# txrx_switch.net
KiCad netlist of a schematic drawn in Altium Designer
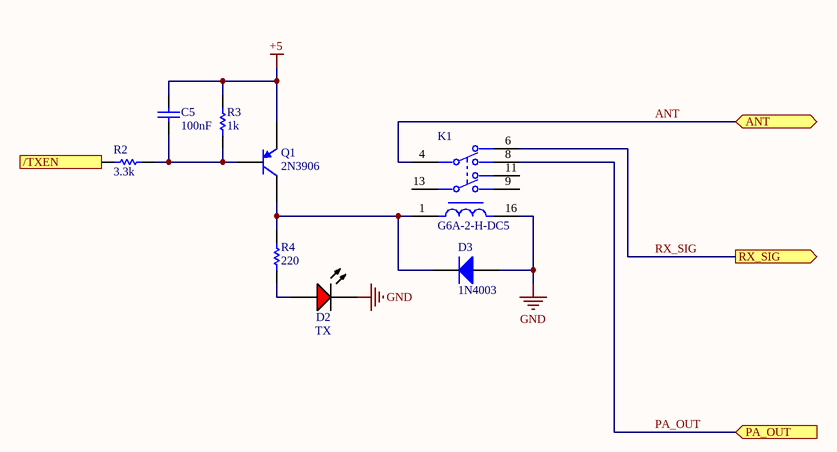
[diagram p0: txrx_switch.SchDoc]

(export (version "E")
  (design (tool "Eeschema 10.0.6"))
  (components
    (comp (ref "C5")
      (value "100nF")
      (footprint "RAD-0.1")
      (description "Capacitor")
      (fields (field (name "Comment") "Cap") (field (name "PUBLISHER") "Altium Limited"))
      (libsource (lib "Miscellaneous Devices") (part "Cap"))
    )
    (comp (ref "D2")
      (value "TX")
      (footprint "AVAG-HLMP-3301-2")
      (description "T-1 3/4 (5 mm) Diffused LED Lamp, 1.9 V, -40 to 100 degC, 2-Pin THD, RoHS, Bulk")
      (fields (field (name "MANUFACTURER") "Avago"))
      (libsource (lib "Altium Content Vault") (part "LED-RED-K1A2-2"))
    )
    (comp (ref "D3")
      (value "1N4003")
      (footprint "DIOD-DO-41-P-2_V")
      (description "1.0 A Rectifier, 15 pF, 200 V, -65 to 150 degC, 2-Pin DO-41 Plastic, RoHS, Tape and Reel")
      (fields (field (name "PARTNUMBER") "1N4003-T") (field (name "MANUFACTURER") "Diodes Inc"))
      (libsource (lib "Altium Content Vault") (part "DIOD-D-A1K2-2"))
    )
    (comp (ref "K1")
      (value "G6A-2-H-DC5")
      (footprint "FP-G6A-2-H-DC5-MFG")
      (description "RELAY GEN PURPOSE DPDT 2A 5VDC")
      (libsource (lib "Altium Content Vault") (part "26c8de10ccef747a418375544070044"))
    )
    (comp (ref "Q1")
      (value "2N3906")
      (footprint "TO-92A")
      (description "PNP General Purpose Amplifier")
      (fields (field (name "PUBLISHER") "Altium Limited"))
      (libsource (lib "Miscellaneous Devices") (part "2N3906"))
    )
    (comp (ref "R2")
      (value "3.3k")
      (footprint "AXIAL-0.4")
      (description "Resistor")
      (fields (field (name "Comment") "Res1") (field (name "PUBLISHER") "Altium Limited"))
      (libsource (lib "Miscellaneous Devices") (part "Res1"))
    )
    (comp (ref "R3")
      (value "1k")
      (footprint "AXIAL-0.4")
      (description "Resistor")
      (fields (field (name "Comment") "Res1") (field (name "PUBLISHER") "Altium Limited"))
      (libsource (lib "Miscellaneous Devices") (part "Res1"))
    )
    (comp (ref "R4")
      (value "220")
      (footprint "AXIAL-0.4")
      (description "Resistor")
      (fields (field (name "Comment") "Res1") (field (name "PUBLISHER") "Altium Limited"))
      (libsource (lib "Miscellaneous Devices") (part "Res1"))
    )
  )
  (nets
    (net (code "1") (name "+5") (class "Default")
      (node (ref "C5") (pin "1") (pinfunction "1_1") (pintype "passive"))
      (node (ref "Q1") (pin "1") (pinfunction "E_1") (pintype "passive"))
      (node (ref "R3") (pin "2") (pinfunction "2_2") (pintype "passive"))
    )
    (net (code "2") (name "/ANT") (class "Default")
      (node (ref "K1") (pin "4") (pinfunction "4_4") (pintype "passive"))
    )
    (net (code "3") (name "/PA_OUT") (class "Default")
      (node (ref "K1") (pin "8") (pinfunction "8_8") (pintype "passive"))
    )
    (net (code "4") (name "/RX_SIG") (class "Default")
      (node (ref "K1") (pin "6") (pinfunction "6_6") (pintype "passive"))
    )
    (net (code "5") (name "/{slash}TXEN") (class "Default")
      (node (ref "R2") (pin "1") (pinfunction "1_1") (pintype "passive"))
    )
    (net (code "6") (name "GND") (class "Default")
      (node (ref "D2") (pin "1") (pinfunction "K_1") (pintype "passive"))
      (node (ref "D3") (pin "1") (pinfunction "A_1") (pintype "passive"))
      (node (ref "K1") (pin "16") (pinfunction "16_16") (pintype "passive"))
    )
    (net (code "7") (name "Net-(D2-A)") (class "Default")
      (node (ref "D2") (pin "2") (pinfunction "A_2") (pintype "passive"))
      (node (ref "R4") (pin "1") (pinfunction "1_1") (pintype "passive"))
    )
    (net (code "8") (name "Net-(D3-K)") (class "Default")
      (node (ref "D3") (pin "2") (pinfunction "K_2") (pintype "passive"))
      (node (ref "K1") (pin "1") (pinfunction "1_1") (pintype "passive"))
      (node (ref "Q1") (pin "3") (pinfunction "C_3") (pintype "passive"))
      (node (ref "R4") (pin "2") (pinfunction "2_2") (pintype "passive"))
    )
    (net (code "9") (name "Net-(Q1-B)") (class "Default")
      (node (ref "C5") (pin "2") (pinfunction "2_2") (pintype "passive"))
      (node (ref "Q1") (pin "2") (pinfunction "B_2") (pintype "passive"))
      (node (ref "R2") (pin "2") (pinfunction "2_2") (pintype "passive"))
      (node (ref "R3") (pin "1") (pinfunction "1_1") (pintype "passive"))
    )
    (net (code "10") (name "unconnected-(K1-Pad9)") (class "Default")
      (node (ref "K1") (pin "9") (pinfunction "9_9") (pintype "passive"))
    )
    (net (code "11") (name "unconnected-(K1-Pad11)") (class "Default")
      (node (ref "K1") (pin "11") (pinfunction "11_11") (pintype "passive"))
    )
    (net (code "12") (name "unconnected-(K1-Pad13)") (class "Default")
      (node (ref "K1") (pin "13") (pinfunction "13_13") (pintype "passive"))
    )
  )
)
